# AIRZAI_BASE_BD_REVC_Sheet1.net
KiCad netlist of a schematic drawn in Altium Designer
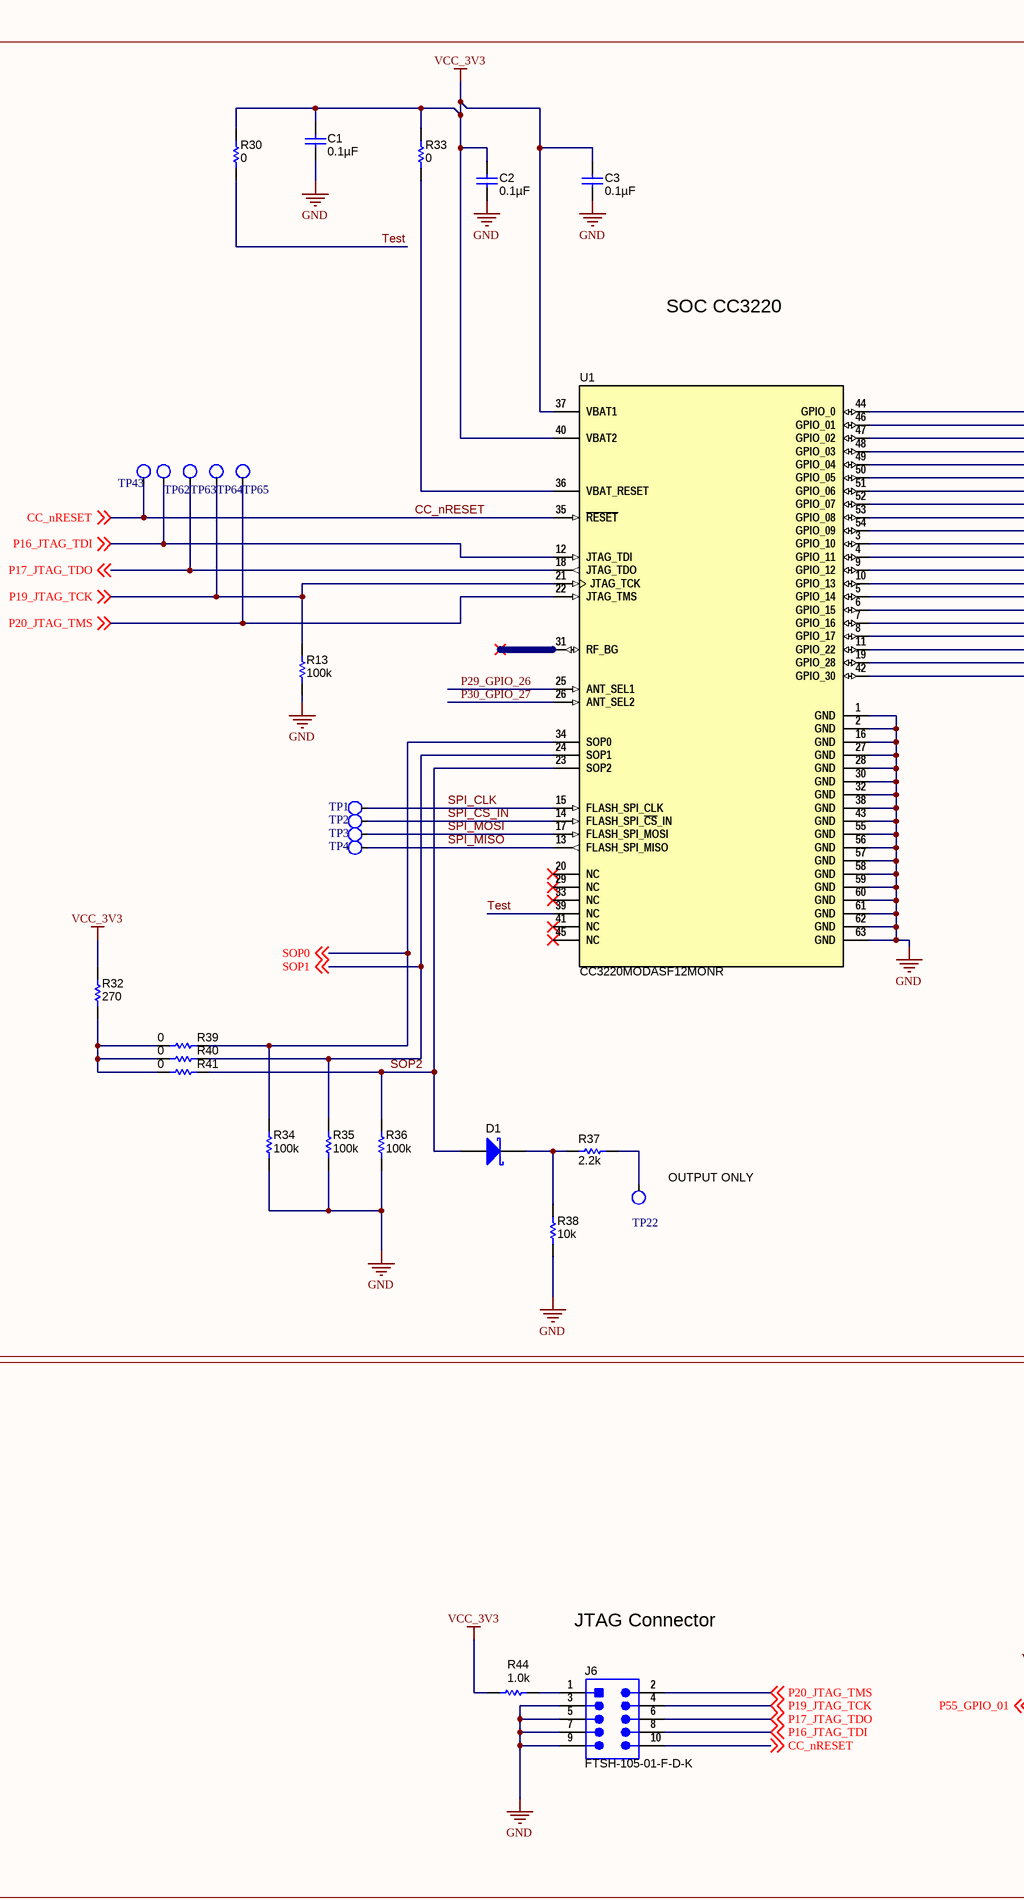
[diagram p0: AIRZAI_BASE_BD_REVC Sheet1.SchDoc, left]
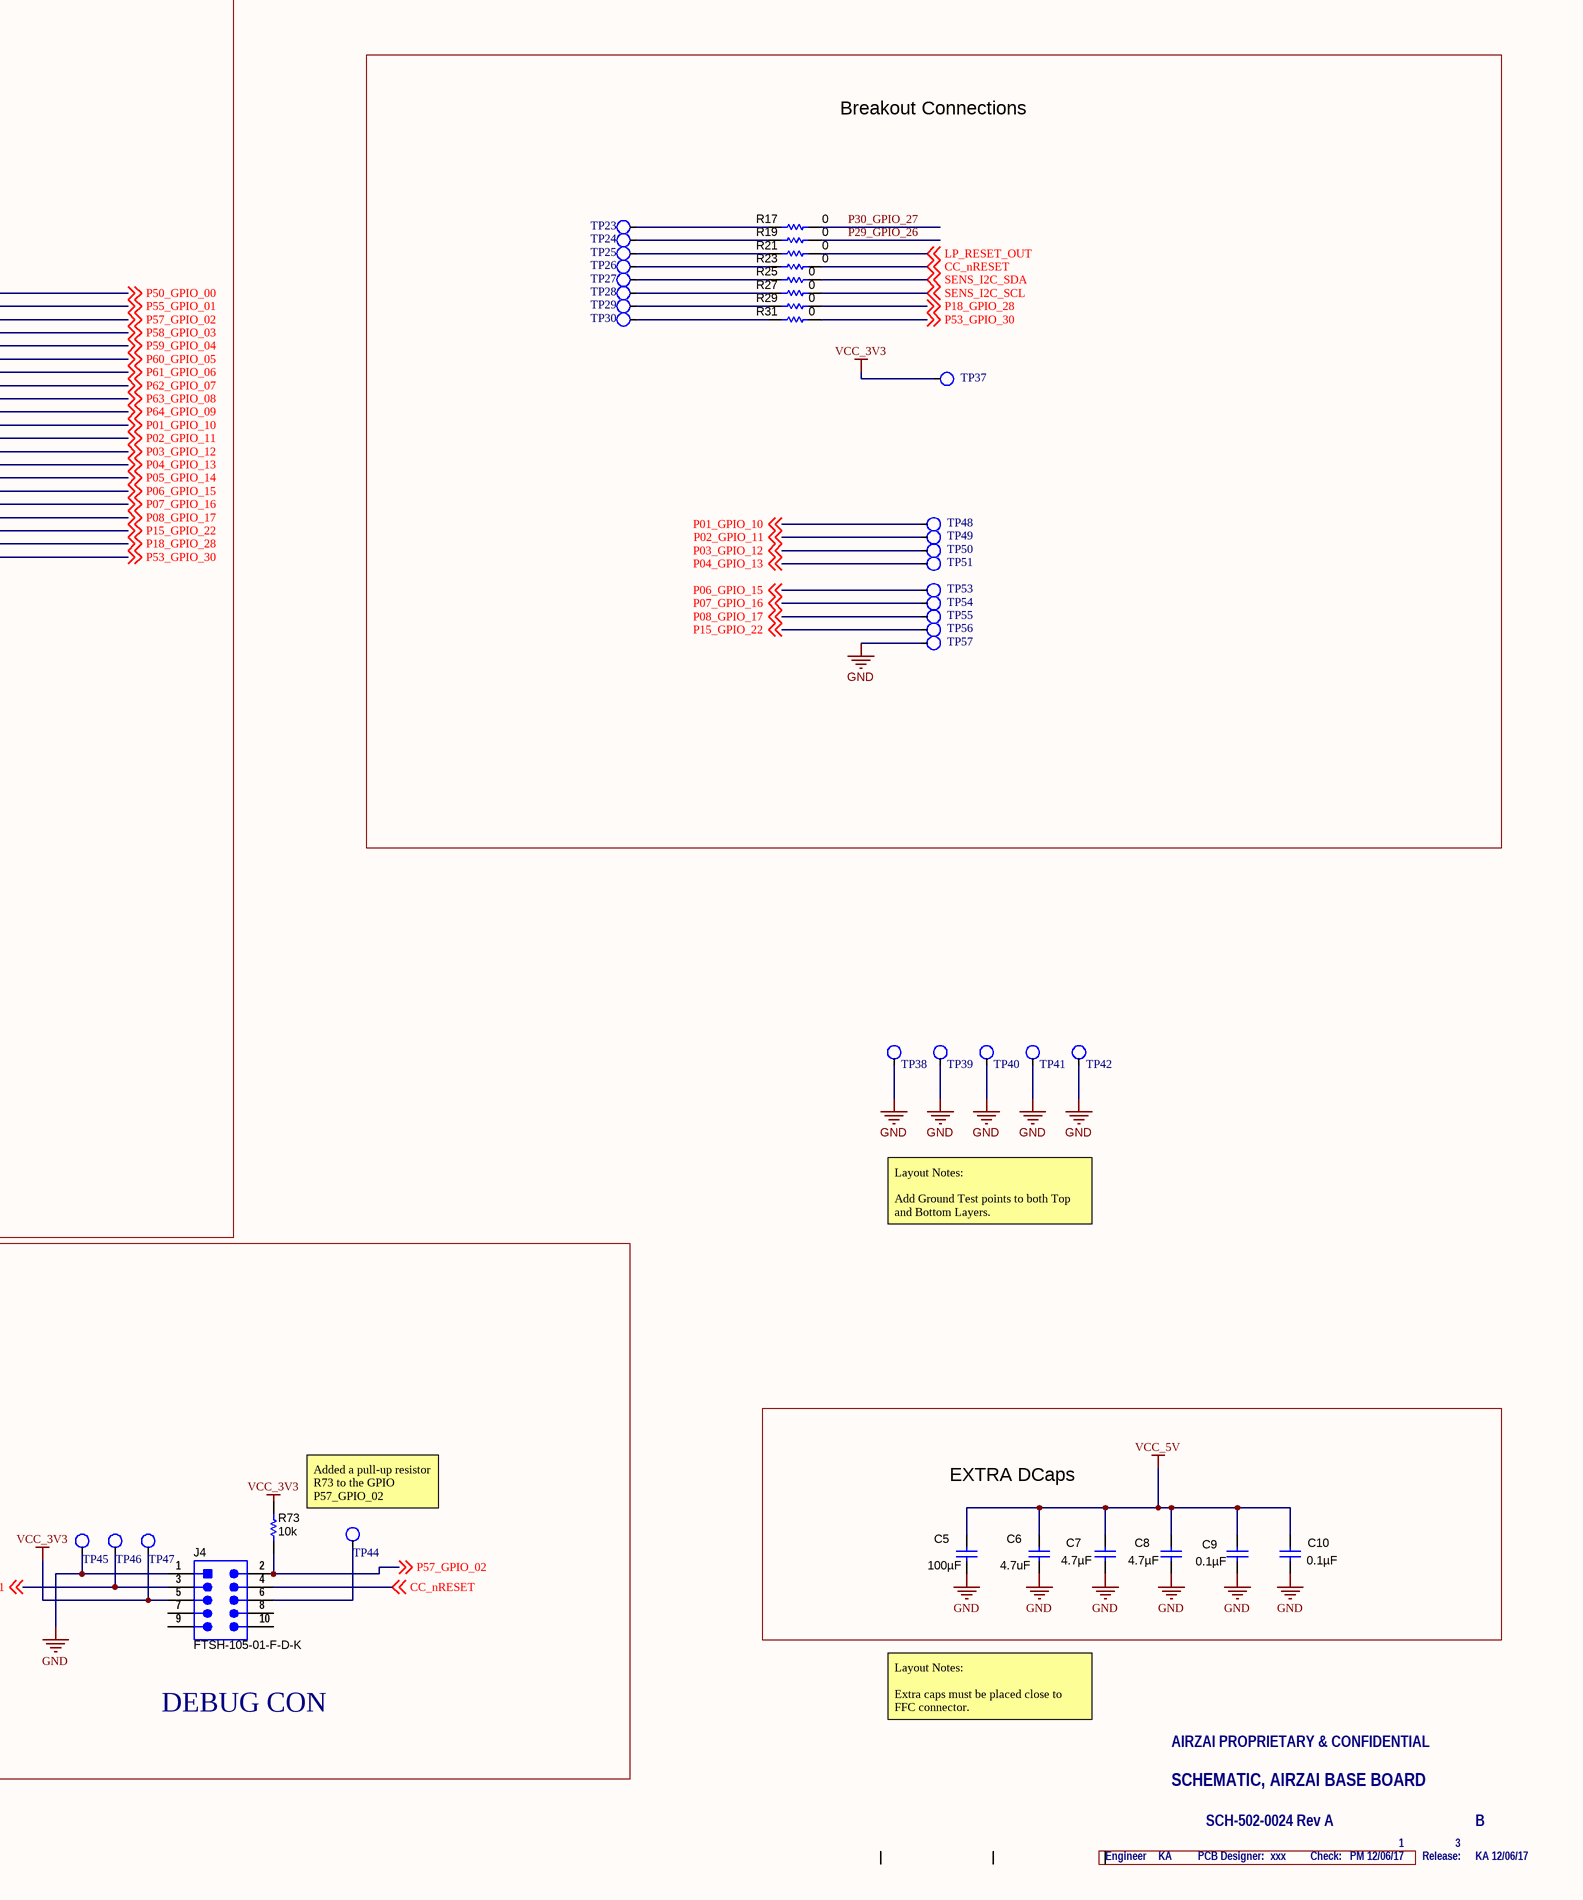
[diagram p1: AIRZAI_BASE_BD_REVC Sheet1.SchDoc, right]

(export (version "E")
  (design (tool "Eeschema 10.0.6"))
  (components
    (comp (ref "C1")
      (value "GRM155R61A104KA01D")
      (footprint "0402")
      (description "CAP, CERM, 0.1 µF, 10 V, +/- 10%, X5R, 0402")
      (fields
        (field (name "VALUEDISPLAYED") "0.1µF")
        (field (name "MANUFACTURER") "MuRata")
        (field (name "PUBLISHER") "Texas Instruments")
      )
      (libsource (lib "Capacitor_Ceramic") (part "GRM155R61A104KA01D"))
    )
    (comp (ref "C2")
      (value "GRM155R61A104KA01D")
      (footprint "0402")
      (description "CAP, CERM, 0.1 µF, 10 V, +/- 10%, X5R, 0402")
      (fields
        (field (name "VALUEDISPLAYED") "0.1µF")
        (field (name "MANUFACTURER") "MuRata")
        (field (name "PUBLISHER") "Texas Instruments")
      )
      (libsource (lib "Capacitor_Ceramic") (part "GRM155R61A104KA01D"))
    )
    (comp (ref "C3")
      (value "GRM155R61A104KA01D")
      (footprint "0402")
      (description "CAP, CERM, 0.1 µF, 10 V, +/- 10%, X5R, 0402")
      (fields
        (field (name "VALUEDISPLAYED") "0.1µF")
        (field (name "MANUFACTURER") "MuRata")
        (field (name "PUBLISHER") "Texas Instruments")
      )
      (libsource (lib "Capacitor_Ceramic") (part "GRM155R61A104KA01D"))
    )
    (comp (ref "C5")
      (value "GRM31CR60J107ME39L")
      (footprint "1206_180")
      (description "CAP, CERM, 100 µF, 6.3 V, +/- 20%, X5R, 1206")
      (fields
        (field (name "VALUEDISPLAYED") "100µF")
        (field (name "MANUFACTURER") "MuRata")
        (field (name "PUBLISHER") "Texas Instruments")
      )
      (libsource (lib "Capacitor_Ceramic") (part "GRM31CR60J107ME39L"))
    )
    (comp (ref "C6")
      (value "4.7uF")
      (footprint "SM0402_BTD.1SM_ACT_H55_CAP_WSS")
      (description "CAP, CERM, 4.7 µF, 6.3 V, +/- 20%, X5R, 0402")
      (fields (field (name "PARTNUMBER") "C1005X5R0J475M050BC") (field (name "MANUFACTURER") "TDK"))
      (libsource (lib "Capacitor_Ceramic") (part "C1005X5R0J475M050BC"))
    )
    (comp (ref "C7")
      (value "C1005X5R0J475M050BC")
      (footprint "SM0402_BTD.1SM_ACT_H55_CAP_WSS")
      (description "CAP, CERM, 4.7 µF, 6.3 V, +/- 20%, X5R, 0402")
      (fields
        (field (name "VALUEDISPLAYED") "4.7µF")
        (field (name "MANUFACTURER") "TDK")
        (field (name "PUBLISHER") "Texas Instruments")
      )
      (libsource (lib "Capacitor_Ceramic") (part "C1005X5R0J475M050BC"))
    )
    (comp (ref "C8")
      (value "C1005X5R0J475M050BC")
      (footprint "SM0402_BTD.1SM_ACT_H55_CAP_WSS")
      (description "CAP, CERM, 4.7 µF, 6.3 V, +/- 20%, X5R, 0402")
      (fields
        (field (name "VALUEDISPLAYED") "4.7µF")
        (field (name "MANUFACTURER") "TDK")
        (field (name "PUBLISHER") "Texas Instruments")
      )
      (libsource (lib "Capacitor_Ceramic") (part "C1005X5R0J475M050BC"))
    )
    (comp (ref "C9")
      (value "C1005X5R1A104K050BA")
      (footprint "SM0402_BTD.1SM_ACT_H55_CAP_WSS")
      (description "CAP, CERM, 0.1 µF, 10 V, +/- 10%, X5R, 0402")
      (fields
        (field (name "VALUEDISPLAYED") "0.1µF")
        (field (name "MANUFACTURER") "TDK")
        (field (name "PUBLISHER") "Texas Instruments")
      )
      (libsource (lib "Capacitor_Ceramic") (part "C1005X5R1A104K050BA"))
    )
    (comp (ref "C10")
      (value "C1005X5R1A104K050BA")
      (footprint "SM0402_BTD.1SM_ACT_H55_CAP_WSS")
      (description "CAP, CERM, 0.1 µF, 10 V, +/- 10%, X5R, 0402")
      (fields
        (field (name "VALUEDISPLAYED") "0.1µF")
        (field (name "MANUFACTURER") "TDK")
        (field (name "PUBLISHER") "Texas Instruments")
      )
      (libsource (lib "Capacitor_Ceramic") (part "C1005X5R1A104K050BA"))
    )
    (comp (ref "D1")
      (value "CD0603-B00340")
      (footprint "Diode_0603")
      (description "Diode, Schottky, 45 V, 0.03 A, 0603 Diode")
      (fields (field (name "MANUFACTURER") "Bourns") (field (name "PUBLISHER") "Texas Instruments"))
      (libsource (lib "Diode") (part "CD0603-B00340"))
    )
    (comp (ref "J4")
      (value "FTSH-105-01-F-D-K")
      (footprint "Samtec_FTSH-105-01-x-D-K")
      (description "Header, 1.27 mm, 5x2, Gold, TH")
      (fields
        (field (name "MANUFACTURER") "Samtec")
        (field (name "SYMBOLCREATOR") "a0412235")
        (field (name "PUBLISHER") "Texas Instruments")
      )
      (libsource (lib "Connectors_Samtec") (part "FTSH-105-01-F-D-K"))
    )
    (comp (ref "J6")
      (value "FTSH-105-01-F-D-K")
      (footprint "Samtec_FTSH-105-01-x-D-K")
      (description "Header, 1.27 mm, 5x2, Gold, TH")
      (fields
        (field (name "MANUFACTURER") "Samtec")
        (field (name "SYMBOLCREATOR") "a0412235")
        (field (name "PUBLISHER") "Texas Instruments")
      )
      (libsource (lib "Connectors_Samtec") (part "FTSH-105-01-F-D-K"))
    )
    (comp (ref "R13")
      (value "CRCW0402100KJNED")
      (footprint "0402")
      (description "RES, 100 k, 5%, 0.063 W, 0402")
      (fields
        (field (name "VALUEDISPLAYED") "100k")
        (field (name "MANUFACTURER") "Vishay-Dale")
        (field (name "PUBLISHER") "Texas Instruments")
      )
      (libsource (lib "Resistor_0402") (part "CRCW0402100KJNED"))
    )
    (comp (ref "R17")
      (value "ERJ-2GE0R00X")
      (footprint "0402")
      (description "RES, 0, 5%, 0.063 W, 0402")
      (fields
        (field (name "VALUEDISPLAYED") "0")
        (field (name "MANUFACTURER") "Panasonic")
        (field (name "PUBLISHER") "Texas Instruments")
      )
      (libsource (lib "Resistor_0402") (part "ERJ-2GE0R00X"))
    )
    (comp (ref "R19")
      (value "ERJ-2GE0R00X")
      (footprint "0402")
      (description "RES, 0, 5%, 0.063 W, 0402")
      (fields
        (field (name "VALUEDISPLAYED") "0")
        (field (name "MANUFACTURER") "Panasonic")
        (field (name "PUBLISHER") "Texas Instruments")
      )
      (libsource (lib "Resistor_0402") (part "ERJ-2GE0R00X"))
    )
    (comp (ref "R21")
      (value "ERJ-2GE0R00X")
      (footprint "0402")
      (description "RES, 0, 5%, 0.063 W, 0402")
      (fields
        (field (name "VALUEDISPLAYED") "0")
        (field (name "MANUFACTURER") "Panasonic")
        (field (name "PUBLISHER") "Texas Instruments")
      )
      (libsource (lib "Resistor_0402") (part "ERJ-2GE0R00X"))
    )
    (comp (ref "R23")
      (value "ERJ-2GE0R00X")
      (footprint "0402")
      (description "RES, 0, 5%, 0.063 W, 0402")
      (fields
        (field (name "VALUEDISPLAYED") "0")
        (field (name "MANUFACTURER") "Panasonic")
        (field (name "PUBLISHER") "Texas Instruments")
      )
      (libsource (lib "Resistor_0402") (part "ERJ-2GE0R00X"))
    )
    (comp (ref "R25")
      (value "ERJ-2GE0R00X")
      (footprint "0402")
      (description "RES, 0, 5%, 0.063 W, 0402")
      (fields
        (field (name "VALUEDISPLAYED") "0")
        (field (name "MANUFACTURER") "Panasonic")
        (field (name "PUBLISHER") "Texas Instruments")
      )
      (libsource (lib "Resistor_0402") (part "ERJ-2GE0R00X"))
    )
    (comp (ref "R27")
      (value "ERJ-2GE0R00X")
      (footprint "0402")
      (description "RES, 0, 5%, 0.063 W, 0402")
      (fields
        (field (name "VALUEDISPLAYED") "0")
        (field (name "MANUFACTURER") "Panasonic")
        (field (name "PUBLISHER") "Texas Instruments")
      )
      (libsource (lib "Resistor_0402") (part "ERJ-2GE0R00X"))
    )
    (comp (ref "R29")
      (value "ERJ-2GE0R00X")
      (footprint "0402")
      (description "RES, 0, 5%, 0.063 W, 0402")
      (fields
        (field (name "VALUEDISPLAYED") "0")
        (field (name "MANUFACTURER") "Panasonic")
        (field (name "PUBLISHER") "Texas Instruments")
      )
      (libsource (lib "Resistor_0402") (part "ERJ-2GE0R00X"))
    )
    (comp (ref "R30")
      (value "RC0603JR-070RL")
      (footprint "0603")
      (description "RES, 0, 5%, 0.1 W, 0603")
      (fields
        (field (name "VALUEDISPLAYED") "0")
        (field (name "MANUFACTURER") "Yageo")
        (field (name "TOLERANCE") "1%")
      )
      (libsource (lib "Resistor_0402") (part "ERJ-2GE0R00X"))
    )
    (comp (ref "R31")
      (value "ERJ-2GE0R00X")
      (footprint "0402")
      (description "RES, 0, 5%, 0.063 W, 0402")
      (fields
        (field (name "VALUEDISPLAYED") "0")
        (field (name "MANUFACTURER") "Panasonic")
        (field (name "PUBLISHER") "Texas Instruments")
      )
      (libsource (lib "Resistor_0402") (part "ERJ-2GE0R00X"))
    )
    (comp (ref "R32")
      (value "CRCW0402270RJNED")
      (footprint "0402")
      (description "RES, 270, 5%, 0.063 W, 0402")
      (fields
        (field (name "VALUEDISPLAYED") "270")
        (field (name "MANUFACTURER") "Vishay-Dale")
        (field (name "PUBLISHER") "Texas Instruments")
      )
      (libsource (lib "Resistor_0402") (part "CRCW0402270RJNED"))
    )
    (comp (ref "R33")
      (value "RC0603JR-070RL")
      (footprint "0603")
      (description "RES, 0, 5%, 0.1 W, 0603")
      (fields
        (field (name "VALUEDISPLAYED") "0")
        (field (name "MANUFACTURER") "Yageo")
        (field (name "TOLERANCE") "1%")
      )
      (libsource (lib "Resistor_0402") (part "ERJ-2GE0R00X"))
    )
    (comp (ref "R34")
      (value "CRCW0402100KJNED")
      (footprint "0402")
      (description "RES, 100 k, 5%, 0.063 W, 0402")
      (fields
        (field (name "VALUEDISPLAYED") "100k")
        (field (name "MANUFACTURER") "Vishay-Dale")
        (field (name "PUBLISHER") "Texas Instruments")
      )
      (libsource (lib "Resistor_0402") (part "CRCW0402100KJNED"))
    )
    (comp (ref "R35")
      (value "CRCW0402100KJNED")
      (footprint "0402")
      (description "RES, 100 k, 5%, 0.063 W, 0402")
      (fields
        (field (name "VALUEDISPLAYED") "100k")
        (field (name "MANUFACTURER") "Vishay-Dale")
        (field (name "PUBLISHER") "Texas Instruments")
      )
      (libsource (lib "Resistor_0402") (part "CRCW0402100KJNED"))
    )
    (comp (ref "R36")
      (value "CRCW0402100KJNED")
      (footprint "0402")
      (description "RES, 100 k, 5%, 0.063 W, 0402")
      (fields
        (field (name "VALUEDISPLAYED") "100k")
        (field (name "MANUFACTURER") "Vishay-Dale")
        (field (name "PUBLISHER") "Texas Instruments")
      )
      (libsource (lib "Resistor_0402") (part "CRCW0402100KJNED"))
    )
    (comp (ref "R37")
      (value "CRCW04022K20JNED")
      (footprint "0402")
      (description "RES, 2.2 k, 5%, 0.063 W, 0402")
      (fields
        (field (name "VALUEDISPLAYED") "2.2k")
        (field (name "MANUFACTURER") "Vishay-Dale")
        (field (name "PUBLISHER") "Texas Instruments")
      )
      (libsource (lib "Resistor_0402") (part "CRCW04022K20JNED"))
    )
    (comp (ref "R38")
      (value "CRCW040210K0JNED")
      (footprint "0402")
      (description "RES, 10 k, 5%, 0.063 W, 0402")
      (fields
        (field (name "VALUEDISPLAYED") "10k")
        (field (name "MANUFACTURER") "Vishay-Dale")
        (field (name "PUBLISHER") "Texas Instruments")
      )
      (libsource (lib "Resistor_0402") (part "CRCW040210K0JNED"))
    )
    (comp (ref "R39")
      (value "RC0603JR-070RL")
      (footprint "0603")
      (description "RES, 0, 5%, 0.1 W, 0603")
      (fields
        (field (name "VALUEDISPLAYED") "0")
        (field (name "MANUFACTURER") "Yageo")
        (field (name "TOLERANCE") "1%")
      )
      (libsource (lib "Resistor_0402") (part "ERJ-2GE0R00X"))
    )
    (comp (ref "R40")
      (value "RC0603JR-070RL")
      (footprint "0603")
      (description "RES, 0, 5%, 0.1 W, 0603")
      (fields
        (field (name "VALUEDISPLAYED") "0")
        (field (name "MANUFACTURER") "Yageo")
        (field (name "TOLERANCE") "1%")
      )
      (libsource (lib "Resistor_0402") (part "ERJ-2GE0R00X"))
    )
    (comp (ref "R41")
      (value "RC0603JR-070RL")
      (footprint "0603")
      (description "RES, 0, 5%, 0.1 W, 0603")
      (fields
        (field (name "VALUEDISPLAYED") "0")
        (field (name "MANUFACTURER") "Yageo")
        (field (name "TOLERANCE") "1%")
      )
      (libsource (lib "Resistor_0402") (part "ERJ-2GE0R00X"))
    )
    (comp (ref "R44")
      (value "CRCW04021K00JNED")
      (footprint "0402")
      (description "RES, 1.0 k, 5%, 0.063 W, 0402")
      (fields
        (field (name "VALUEDISPLAYED") "1.0k")
        (field (name "MANUFACTURER") "Vishay-Dale")
        (field (name "PUBLISHER") "Texas Instruments")
      )
      (libsource (lib "Resistor_0402") (part "CRCW04021K00JNED"))
    )
    (comp (ref "R73")
      (value "CRCW040210K0JNED")
      (footprint "0402")
      (description "RES, 10 k, 5%, 0.063 W, 0402")
      (fields
        (field (name "VALUEDISPLAYED") "10k")
        (field (name "MANUFACTURER") "Vishay-Dale")
        (field (name "PUBLISHER") "Texas Instruments")
      )
      (libsource (lib "Resistor_0402") (part "CRCW040210K0JNED"))
    )
    (comp (ref "TP1")
      (value "WIREPT")
      (footprint "TP_0.9MM")
      (libsource (lib "EAGLE_CAD_Library") (part "WIREPT"))
    )
    (comp (ref "TP2")
      (value "WIREPT")
      (footprint "TP_0.9MM")
      (libsource (lib "EAGLE_CAD_Library") (part "WIREPT"))
    )
    (comp (ref "TP3")
      (value "WIREPT")
      (footprint "TP_0.9MM")
      (libsource (lib "EAGLE_CAD_Library") (part "WIREPT"))
    )
    (comp (ref "TP4")
      (value "WIREPT")
      (footprint "TP_0.9MM")
      (libsource (lib "EAGLE_CAD_Library") (part "WIREPT"))
    )
    (comp (ref "TP22")
      (value "WIREPT")
      (footprint "TP_0.9MM")
      (libsource (lib "EAGLE_CAD_Library") (part "WIREPT"))
    )
    (comp (ref "TP23")
      (value "WIREPT")
      (footprint "TP_0.9MM")
      (libsource (lib "EAGLE_CAD_Library") (part "WIREPT"))
    )
    (comp (ref "TP24")
      (value "WIREPT")
      (footprint "TP_0.9MM")
      (libsource (lib "EAGLE_CAD_Library") (part "WIREPT"))
    )
    (comp (ref "TP25")
      (value "WIREPT")
      (footprint "TP_0.9MM")
      (libsource (lib "EAGLE_CAD_Library") (part "WIREPT"))
    )
    (comp (ref "TP26")
      (value "WIREPT")
      (footprint "TP_0.9MM")
      (libsource (lib "EAGLE_CAD_Library") (part "WIREPT"))
    )
    (comp (ref "TP27")
      (value "WIREPT")
      (footprint "TP_0.9MM")
      (libsource (lib "EAGLE_CAD_Library") (part "WIREPT"))
    )
    (comp (ref "TP28")
      (value "WIREPT")
      (footprint "TP_0.9MM")
      (libsource (lib "EAGLE_CAD_Library") (part "WIREPT"))
    )
    (comp (ref "TP29")
      (value "WIREPT")
      (footprint "TP_0.9MM")
      (libsource (lib "EAGLE_CAD_Library") (part "WIREPT"))
    )
    (comp (ref "TP30")
      (value "WIREPT")
      (footprint "TP_0.9MM")
      (libsource (lib "EAGLE_CAD_Library") (part "WIREPT"))
    )
    (comp (ref "TP37")
      (value "WIREPT")
      (footprint "TP_0.9MM")
      (libsource (lib "EAGLE_CAD_Library") (part "WIREPT"))
    )
    (comp (ref "TP38")
      (value "WIREPT")
      (footprint "TP_0.9MM")
      (libsource (lib "EAGLE_CAD_Library") (part "WIREPT"))
    )
    (comp (ref "TP39")
      (value "WIREPT")
      (footprint "TP_0.9MM")
      (libsource (lib "EAGLE_CAD_Library") (part "WIREPT"))
    )
    (comp (ref "TP40")
      (value "WIREPT")
      (footprint "TP_0.9MM")
      (libsource (lib "EAGLE_CAD_Library") (part "WIREPT"))
    )
    (comp (ref "TP41")
      (value "WIREPT")
      (footprint "TP_0.9MM")
      (libsource (lib "EAGLE_CAD_Library") (part "WIREPT"))
    )
    (comp (ref "TP42")
      (value "WIREPT")
      (footprint "TP_0.9MM")
      (libsource (lib "EAGLE_CAD_Library") (part "WIREPT"))
    )
    (comp (ref "TP43")
      (value "WIREPT")
      (footprint "TP_0.9MM")
      (libsource (lib "EAGLE_CAD_Library") (part "WIREPT"))
    )
    (comp (ref "TP44")
      (value "WIREPT")
      (footprint "TP_0.9MM")
      (libsource (lib "EAGLE_CAD_Library") (part "WIREPT"))
    )
    (comp (ref "TP45")
      (value "WIREPT")
      (footprint "TP_0.9MM")
      (libsource (lib "EAGLE_CAD_Library") (part "WIREPT"))
    )
    (comp (ref "TP46")
      (value "WIREPT")
      (footprint "TP_0.9MM")
      (libsource (lib "EAGLE_CAD_Library") (part "WIREPT"))
    )
    (comp (ref "TP47")
      (value "WIREPT")
      (footprint "TP_0.9MM")
      (libsource (lib "EAGLE_CAD_Library") (part "WIREPT"))
    )
    (comp (ref "TP48")
      (value "WIREPT")
      (footprint "TP_0.9MM")
      (libsource (lib "EAGLE_CAD_Library") (part "WIREPT"))
    )
    (comp (ref "TP49")
      (value "WIREPT")
      (footprint "TP_0.9MM")
      (libsource (lib "EAGLE_CAD_Library") (part "WIREPT"))
    )
    (comp (ref "TP50")
      (value "WIREPT")
      (footprint "TP_0.9MM")
      (libsource (lib "EAGLE_CAD_Library") (part "WIREPT"))
    )
    (comp (ref "TP51")
      (value "WIREPT")
      (footprint "TP_0.9MM")
      (libsource (lib "EAGLE_CAD_Library") (part "WIREPT"))
    )
    (comp (ref "TP53")
      (value "WIREPT")
      (footprint "TP_0.9MM")
      (libsource (lib "EAGLE_CAD_Library") (part "WIREPT"))
    )
    (comp (ref "TP54")
      (value "WIREPT")
      (footprint "TP_0.9MM")
      (libsource (lib "EAGLE_CAD_Library") (part "WIREPT"))
    )
    (comp (ref "TP55")
      (value "WIREPT")
      (footprint "TP_0.9MM")
      (libsource (lib "EAGLE_CAD_Library") (part "WIREPT"))
    )
    (comp (ref "TP56")
      (value "WIREPT")
      (footprint "TP_0.9MM")
      (libsource (lib "EAGLE_CAD_Library") (part "WIREPT"))
    )
    (comp (ref "TP57")
      (value "WIREPT")
      (footprint "TP_0.9MM")
      (libsource (lib "EAGLE_CAD_Library") (part "WIREPT"))
    )
    (comp (ref "TP62")
      (value "WIREPT")
      (footprint "TP_0.9MM")
      (libsource (lib "EAGLE_CAD_Library") (part "WIREPT"))
    )
    (comp (ref "TP63")
      (value "WIREPT")
      (footprint "TP_0.9MM")
      (libsource (lib "EAGLE_CAD_Library") (part "WIREPT"))
    )
    (comp (ref "TP64")
      (value "WIREPT")
      (footprint "TP_0.9MM")
      (libsource (lib "EAGLE_CAD_Library") (part "WIREPT"))
    )
    (comp (ref "TP65")
      (value "WIREPT")
      (footprint "TP_0.9MM")
      (libsource (lib "EAGLE_CAD_Library") (part "WIREPT"))
    )
    (comp (ref "U1")
      (value "CC3220MODASF12MONR")
      (footprint "MON0063A")
      (fields
        (field (name "ALTERNATE PARTNUMBER") "XCC3220MODASF12MONR")
        (field (name "MANUFACTURER") "Texas Instruments")
        (field (name "SYMBOLCREATOR") "Altium")
        (field (name "PUBLISHER") "Texas Instruments")
      )
      (libsource (lib "TI_Pre_RTM") (part "CC3220MODASF12MONR"))
    )
  )
  (nets
    (net (code "1") (name "/P29_GPIO_26") (class "Default")
      (node (ref "R19") (pin "2") (pinfunction "2_2") (pintype "passive"))
      (node (ref "U1") (pin "25") (pinfunction "ANT_SEL1_25") (pintype "input"))
    )
    (net (code "2") (name "/P30_GPIO_27") (class "Default")
      (node (ref "R17") (pin "2") (pinfunction "2_2") (pintype "passive"))
      (node (ref "U1") (pin "26") (pinfunction "ANT_SEL2_26") (pintype "input"))
    )
    (net (code "3") (name "/SOP2") (class "Default")
      (node (ref "D1") (pin "2") (pinfunction "A_2") (pintype "passive"))
      (node (ref "R36") (pin "1") (pinfunction "1_1") (pintype "passive"))
      (node (ref "R41") (pin "1") (pinfunction "1_1") (pintype "passive"))
      (node (ref "U1") (pin "23") (pinfunction "SOP2_23") (pintype "passive"))
    )
    (net (code "4") (name "/SPI_CLK") (class "Default")
      (node (ref "TP1") (pin "1") (pinfunction "1_1") (pintype "passive"))
      (node (ref "U1") (pin "15") (pinfunction "FLASH_SPI_CLK_15") (pintype "input"))
    )
    (net (code "5") (name "/SPI_CS_IN") (class "Default")
      (node (ref "TP2") (pin "1") (pinfunction "1_1") (pintype "passive"))
      (node (ref "U1") (pin "14") (pinfunction "FLASH_SPI_~{CS}_IN_14") (pintype "input"))
    )
    (net (code "6") (name "/SPI_MISO") (class "Default")
      (node (ref "TP4") (pin "1") (pinfunction "1_1") (pintype "passive"))
      (node (ref "U1") (pin "13") (pinfunction "FLASH_SPI_MISO_13") (pintype "output"))
    )
    (net (code "7") (name "/SPI_MOSI") (class "Default")
      (node (ref "TP3") (pin "1") (pinfunction "1_1") (pintype "passive"))
      (node (ref "U1") (pin "17") (pinfunction "FLASH_SPI_MOSI_17") (pintype "input"))
    )
    (net (code "8") (name "/Test") (class "Default")
      (node (ref "R30") (pin "1") (pinfunction "1_1") (pintype "passive"))
      (node (ref "U1") (pin "39") (pinfunction "NC_39") (pintype "passive"))
    )
    (net (code "9") (name "CC_nRESET") (class "Default")
      (node (ref "J4") (pin "4") (pinfunction "4_4") (pintype "passive"))
      (node (ref "J6") (pin "10") (pinfunction "10_10") (pintype "passive"))
      (node (ref "R23") (pin "2") (pinfunction "2_2") (pintype "passive"))
      (node (ref "TP43") (pin "1") (pinfunction "1_1") (pintype "passive"))
      (node (ref "U1") (pin "35") (pinfunction "RESET_35") (pintype "input"))
    )
    (net (code "10") (name "GND") (class "Default")
      (node (ref "C1") (pin "2") (pinfunction "2_2") (pintype "passive"))
      (node (ref "C10") (pin "2") (pinfunction "2_2") (pintype "passive"))
      (node (ref "C2") (pin "2") (pinfunction "2_2") (pintype "passive"))
      (node (ref "C3") (pin "2") (pinfunction "2_2") (pintype "passive"))
      (node (ref "C5") (pin "2") (pinfunction "2_2") (pintype "passive"))
      (node (ref "C6") (pin "2") (pinfunction "2_2") (pintype "passive"))
      (node (ref "C7") (pin "2") (pinfunction "2_2") (pintype "passive"))
      (node (ref "C8") (pin "2") (pinfunction "2_2") (pintype "passive"))
      (node (ref "C9") (pin "2") (pinfunction "2_2") (pintype "passive"))
      (node (ref "J4") (pin "1") (pinfunction "1_1") (pintype "passive"))
      (node (ref "J6") (pin "3") (pinfunction "3_3") (pintype "passive"))
      (node (ref "J6") (pin "5") (pinfunction "5_5") (pintype "passive"))
      (node (ref "J6") (pin "7") (pinfunction "7_7") (pintype "passive"))
      (node (ref "J6") (pin "9") (pinfunction "9_9") (pintype "passive"))
      (node (ref "R13") (pin "2") (pinfunction "2_2") (pintype "passive"))
      (node (ref "R34") (pin "1") (pinfunction "1_1") (pintype "passive"))
      (node (ref "R35") (pin "2") (pinfunction "2_2") (pintype "passive"))
      (node (ref "R36") (pin "2") (pinfunction "2_2") (pintype "passive"))
      (node (ref "R38") (pin "2") (pinfunction "2_2") (pintype "passive"))
      (node (ref "TP38") (pin "1") (pinfunction "1_1") (pintype "passive"))
      (node (ref "TP39") (pin "1") (pinfunction "1_1") (pintype "passive"))
      (node (ref "TP40") (pin "1") (pinfunction "1_1") (pintype "passive"))
      (node (ref "TP41") (pin "1") (pinfunction "1_1") (pintype "passive"))
      (node (ref "TP42") (pin "1") (pinfunction "1_1") (pintype "passive"))
      (node (ref "TP45") (pin "1") (pinfunction "1_1") (pintype "passive"))
      (node (ref "TP57") (pin "1") (pinfunction "1_1") (pintype "passive"))
      (node (ref "U1") (pin "1") (pinfunction "GND_1") (pintype "power_in"))
      (node (ref "U1") (pin "16") (pinfunction "GND_16") (pintype "power_in"))
      (node (ref "U1") (pin "2") (pinfunction "GND_2") (pintype "power_in"))
      (node (ref "U1") (pin "27") (pinfunction "GND_27") (pintype "power_in"))
      (node (ref "U1") (pin "28") (pinfunction "GND_28") (pintype "power_in"))
      (node (ref "U1") (pin "30") (pinfunction "GND_30") (pintype "power_in"))
      (node (ref "U1") (pin "32") (pinfunction "GND_32") (pintype "power_in"))
      (node (ref "U1") (pin "38") (pinfunction "GND_38") (pintype "power_in"))
      (node (ref "U1") (pin "43") (pinfunction "GND_43") (pintype "power_in"))
      (node (ref "U1") (pin "55") (pinfunction "GND_55") (pintype "power_in"))
      (node (ref "U1") (pin "56") (pinfunction "GND_56") (pintype "power_in"))
      (node (ref "U1") (pin "57") (pinfunction "GND_57") (pintype "power_in"))
      (node (ref "U1") (pin "58") (pinfunction "GND_58") (pintype "power_in"))
      (node (ref "U1") (pin "59") (pinfunction "GND_59") (pintype "power_in"))
      (node (ref "U1") (pin "60") (pinfunction "GND_60") (pintype "power_in"))
      (node (ref "U1") (pin "61") (pinfunction "GND_61") (pintype "power_in"))
      (node (ref "U1") (pin "62") (pinfunction "GND_62") (pintype "power_in"))
      (node (ref "U1") (pin "63") (pinfunction "GND_63") (pintype "power_in"))
    )
    (net (code "11") (name "LP_RESET_OUT") (class "Default")
      (node (ref "R21") (pin "2") (pinfunction "2_2") (pintype "passive"))
    )
    (net (code "12") (name "Net-(D1-K)") (class "Default")
      (node (ref "D1") (pin "1") (pinfunction "K_1") (pintype "passive"))
      (node (ref "R37") (pin "1") (pinfunction "1_1") (pintype "passive"))
      (node (ref "R38") (pin "1") (pinfunction "1_1") (pintype "passive"))
    )
    (net (code "13") (name "Net-(J4-Pad6)") (class "Default")
      (node (ref "J4") (pin "6") (pinfunction "6_6") (pintype "passive"))
      (node (ref "TP44") (pin "1") (pinfunction "1_1") (pintype "passive"))
    )
    (net (code "14") (name "Net-(J6-Pad1)") (class "Default")
      (node (ref "J6") (pin "1") (pinfunction "1_1") (pintype "passive"))
      (node (ref "R44") (pin "2") (pinfunction "2_2") (pintype "passive"))
    )
    (net (code "15") (name "Net-(R17-Pad1)") (class "Default")
      (node (ref "R17") (pin "1") (pinfunction "1_1") (pintype "passive"))
      (node (ref "TP23") (pin "1") (pinfunction "1_1") (pintype "passive"))
    )
    (net (code "16") (name "Net-(R19-Pad1)") (class "Default")
      (node (ref "R19") (pin "1") (pinfunction "1_1") (pintype "passive"))
      (node (ref "TP24") (pin "1") (pinfunction "1_1") (pintype "passive"))
    )
    (net (code "17") (name "Net-(R21-Pad1)") (class "Default")
      (node (ref "R21") (pin "1") (pinfunction "1_1") (pintype "passive"))
      (node (ref "TP25") (pin "1") (pinfunction "1_1") (pintype "passive"))
    )
    (net (code "18") (name "Net-(R23-Pad1)") (class "Default")
      (node (ref "R23") (pin "1") (pinfunction "1_1") (pintype "passive"))
      (node (ref "TP26") (pin "1") (pinfunction "1_1") (pintype "passive"))
    )
    (net (code "19") (name "Net-(R25-Pad1)") (class "Default")
      (node (ref "R25") (pin "1") (pinfunction "1_1") (pintype "passive"))
      (node (ref "TP27") (pin "1") (pinfunction "1_1") (pintype "passive"))
    )
    (net (code "20") (name "Net-(R27-Pad1)") (class "Default")
      (node (ref "R27") (pin "1") (pinfunction "1_1") (pintype "passive"))
      (node (ref "TP28") (pin "1") (pinfunction "1_1") (pintype "passive"))
    )
    (net (code "21") (name "Net-(R29-Pad1)") (class "Default")
      (node (ref "R29") (pin "1") (pinfunction "1_1") (pintype "passive"))
      (node (ref "TP29") (pin "1") (pinfunction "1_1") (pintype "passive"))
    )
    (net (code "22") (name "Net-(R31-Pad1)") (class "Default")
      (node (ref "R31") (pin "1") (pinfunction "1_1") (pintype "passive"))
      (node (ref "TP30") (pin "1") (pinfunction "1_1") (pintype "passive"))
    )
    (net (code "23") (name "Net-(R32-Pad2)") (class "Default")
      (node (ref "R32") (pin "2") (pinfunction "2_2") (pintype "passive"))
      (node (ref "R39") (pin "2") (pinfunction "2_2") (pintype "passive"))
      (node (ref "R40") (pin "2") (pinfunction "2_2") (pintype "passive"))
      (node (ref "R41") (pin "2") (pinfunction "2_2") (pintype "passive"))
    )
    (net (code "24") (name "Net-(R37-Pad2)") (class "Default")
      (node (ref "R37") (pin "2") (pinfunction "2_2") (pintype "passive"))
      (node (ref "TP22") (pin "1") (pinfunction "1_1") (pintype "passive"))
    )
    (net (code "25") (name "Net-(U1-VBAT_RESET)") (class "Default")
      (node (ref "R33") (pin "1") (pinfunction "1_1") (pintype "passive"))
      (node (ref "U1") (pin "36") (pinfunction "VBAT_RESET_36") (pintype "passive"))
    )
    (net (code "26") (name "P01_GPIO_10") (class "Default")
      (node (ref "TP48") (pin "1") (pinfunction "1_1") (pintype "passive"))
      (node (ref "U1") (pin "3") (pinfunction "GPIO_10_3") (pintype "bidirectional"))
    )
    (net (code "27") (name "P02_GPIO_11") (class "Default")
      (node (ref "TP49") (pin "1") (pinfunction "1_1") (pintype "passive"))
      (node (ref "U1") (pin "4") (pinfunction "GPIO_11_4") (pintype "bidirectional"))
    )
    (net (code "28") (name "P03_GPIO_12") (class "Default")
      (node (ref "TP50") (pin "1") (pinfunction "1_1") (pintype "passive"))
      (node (ref "U1") (pin "9") (pinfunction "GPIO_12_9") (pintype "bidirectional"))
    )
    (net (code "29") (name "P04_GPIO_13") (class "Default")
      (node (ref "TP51") (pin "1") (pinfunction "1_1") (pintype "passive"))
      (node (ref "U1") (pin "10") (pinfunction "GPIO_13_10") (pintype "bidirectional"))
    )
    (net (code "30") (name "P05_GPIO_14") (class "Default")
      (node (ref "U1") (pin "5") (pinfunction "GPIO_14_5") (pintype "bidirectional"))
    )
    (net (code "31") (name "P06_GPIO_15") (class "Default")
      (node (ref "TP53") (pin "1") (pinfunction "1_1") (pintype "passive"))
      (node (ref "U1") (pin "6") (pinfunction "GPIO_15_6") (pintype "bidirectional"))
    )
    (net (code "32") (name "P07_GPIO_16") (class "Default")
      (node (ref "TP54") (pin "1") (pinfunction "1_1") (pintype "passive"))
      (node (ref "U1") (pin "7") (pinfunction "GPIO_16_7") (pintype "bidirectional"))
    )
    (net (code "33") (name "P08_GPIO_17") (class "Default")
      (node (ref "TP55") (pin "1") (pinfunction "1_1") (pintype "passive"))
      (node (ref "U1") (pin "8") (pinfunction "GPIO_17_8") (pintype "bidirectional"))
    )
    (net (code "34") (name "P15_GPIO_22") (class "Default")
      (node (ref "TP56") (pin "1") (pinfunction "1_1") (pintype "passive"))
      (node (ref "U1") (pin "11") (pinfunction "GPIO_22_11") (pintype "bidirectional"))
    )
    (net (code "35") (name "P16_JTAG_TDI") (class "Default")
      (node (ref "J6") (pin "8") (pinfunction "8_8") (pintype "passive"))
      (node (ref "TP62") (pin "1") (pinfunction "1_1") (pintype "passive"))
      (node (ref "U1") (pin "12") (pinfunction "JTAG_TDI_12") (pintype "input"))
    )
    (net (code "36") (name "P17_JTAG_TDO") (class "Default")
      (node (ref "J6") (pin "6") (pinfunction "6_6") (pintype "passive"))
      (node (ref "TP63") (pin "1") (pinfunction "1_1") (pintype "passive"))
      (node (ref "U1") (pin "18") (pinfunction "JTAG_TDO_18") (pintype "output"))
    )
    (net (code "37") (name "P18_GPIO_28") (class "Default")
      (node (ref "R29") (pin "2") (pinfunction "2_2") (pintype "passive"))
      (node (ref "U1") (pin "19") (pinfunction "GPIO_28_19") (pintype "bidirectional"))
    )
    (net (code "38") (name "P19_JTAG_TCK") (class "Default")
      (node (ref "J6") (pin "4") (pinfunction "4_4") (pintype "passive"))
      (node (ref "R13") (pin "1") (pinfunction "1_1") (pintype "passive"))
      (node (ref "TP64") (pin "1") (pinfunction "1_1") (pintype "passive"))
      (node (ref "U1") (pin "21") (pinfunction "JTAG_TCK_21") (pintype "input"))
    )
    (net (code "39") (name "P20_JTAG_TMS") (class "Default")
      (node (ref "J6") (pin "2") (pinfunction "2_2") (pintype "passive"))
      (node (ref "TP65") (pin "1") (pinfunction "1_1") (pintype "passive"))
      (node (ref "U1") (pin "22") (pinfunction "JTAG_TMS_22") (pintype "input"))
    )
    (net (code "40") (name "P50_GPIO_00") (class "Default")
      (node (ref "U1") (pin "44") (pinfunction "GPIO_0_44") (pintype "bidirectional"))
    )
    (net (code "41") (name "P53_GPIO_30") (class "Default")
      (node (ref "R31") (pin "2") (pinfunction "2_2") (pintype "passive"))
      (node (ref "U1") (pin "42") (pinfunction "GPIO_30_42") (pintype "bidirectional"))
    )
    (net (code "42") (name "P55_GPIO_01") (class "Default")
      (node (ref "J4") (pin "3") (pinfunction "3_3") (pintype "passive"))
      (node (ref "TP46") (pin "1") (pinfunction "1_1") (pintype "passive"))
      (node (ref "U1") (pin "46") (pinfunction "GPIO_01_46") (pintype "bidirectional"))
    )
    (net (code "43") (name "P57_GPIO_02") (class "Default")
      (node (ref "J4") (pin "2") (pinfunction "2_2") (pintype "passive"))
      (node (ref "R73") (pin "2") (pinfunction "2_2") (pintype "passive"))
      (node (ref "U1") (pin "47") (pinfunction "GPIO_02_47") (pintype "bidirectional"))
    )
    (net (code "44") (name "P58_GPIO_03") (class "Default")
      (node (ref "U1") (pin "48") (pinfunction "GPIO_03_48") (pintype "bidirectional"))
    )
    (net (code "45") (name "P59_GPIO_04") (class "Default")
      (node (ref "U1") (pin "49") (pinfunction "GPIO_04_49") (pintype "bidirectional"))
    )
    (net (code "46") (name "P60_GPIO_05") (class "Default")
      (node (ref "U1") (pin "50") (pinfunction "GPIO_05_50") (pintype "bidirectional"))
    )
    (net (code "47") (name "P61_GPIO_06") (class "Default")
      (node (ref "U1") (pin "51") (pinfunction "GPIO_06_51") (pintype "bidirectional"))
    )
    (net (code "48") (name "P62_GPIO_07") (class "Default")
      (node (ref "U1") (pin "52") (pinfunction "GPIO_07_52") (pintype "bidirectional"))
    )
    (net (code "49") (name "P63_GPIO_08") (class "Default")
      (node (ref "U1") (pin "53") (pinfunction "GPIO_08_53") (pintype "bidirectional"))
    )
    (net (code "50") (name "P64_GPIO_09") (class "Default")
      (node (ref "U1") (pin "54") (pinfunction "GPIO_09_54") (pintype "bidirectional"))
    )
    (net (code "51") (name "SENS_I2C_SCL") (class "Default")
      (node (ref "R27") (pin "2") (pinfunction "2_2") (pintype "passive"))
    )
    (net (code "52") (name "SENS_I2C_SDA") (class "Default")
      (node (ref "R25") (pin "2") (pinfunction "2_2") (pintype "passive"))
    )
    (net (code "53") (name "SOP0") (class "Default")
      (node (ref "R34") (pin "2") (pinfunction "2_2") (pintype "passive"))
      (node (ref "R39") (pin "1") (pinfunction "1_1") (pintype "passive"))
      (node (ref "U1") (pin "34") (pinfunction "SOP0_34") (pintype "passive"))
    )
    (net (code "54") (name "SOP1") (class "Default")
      (node (ref "R35") (pin "1") (pinfunction "1_1") (pintype "passive"))
      (node (ref "R40") (pin "1") (pinfunction "1_1") (pintype "passive"))
      (node (ref "U1") (pin "24") (pinfunction "SOP1_24") (pintype "passive"))
    )
    (net (code "55") (name "VCC_3V3") (class "Default")
      (node (ref "C1") (pin "1") (pinfunction "1_1") (pintype "passive"))
      (node (ref "C2") (pin "1") (pinfunction "1_1") (pintype "passive"))
      (node (ref "C3") (pin "1") (pinfunction "1_1") (pintype "passive"))
      (node (ref "J4") (pin "5") (pinfunction "5_5") (pintype "passive"))
      (node (ref "R30") (pin "2") (pinfunction "2_2") (pintype "passive"))
      (node (ref "R32") (pin "1") (pinfunction "1_1") (pintype "passive"))
      (node (ref "R33") (pin "2") (pinfunction "2_2") (pintype "passive"))
      (node (ref "R44") (pin "1") (pinfunction "1_1") (pintype "passive"))
      (node (ref "TP37") (pin "1") (pinfunction "1_1") (pintype "passive"))
      (node (ref "TP47") (pin "1") (pinfunction "1_1") (pintype "passive"))
      (node (ref "U1") (pin "37") (pinfunction "VBAT1_37") (pintype "power_in"))
      (node (ref "U1") (pin "40") (pinfunction "VBAT2_40") (pintype "power_in"))
    )
    (net (code "56") (name "VCC_5V") (class "Default")
      (node (ref "C10") (pin "1") (pinfunction "1_1") (pintype "passive"))
      (node (ref "C5") (pin "1") (pinfunction "1_1") (pintype "passive"))
      (node (ref "C6") (pin "1") (pinfunction "1_1") (pintype "passive"))
      (node (ref "C7") (pin "1") (pinfunction "1_1") (pintype "passive"))
      (node (ref "C8") (pin "1") (pinfunction "1_1") (pintype "passive"))
      (node (ref "C9") (pin "1") (pinfunction "1_1") (pintype "passive"))
    )
    (net (code "57") (name "unconnected-(J4-Pad7)") (class "Default")
      (node (ref "J4") (pin "7") (pinfunction "7_7") (pintype "passive"))
    )
    (net (code "58") (name "unconnected-(J4-Pad8)") (class "Default")
      (node (ref "J4") (pin "8") (pinfunction "8_8") (pintype "passive"))
    )
    (net (code "59") (name "unconnected-(J4-Pad9)") (class "Default")
      (node (ref "J4") (pin "9") (pinfunction "9_9") (pintype "passive"))
    )
    (net (code "60") (name "unconnected-(J4-Pad10)") (class "Default")
      (node (ref "J4") (pin "10") (pinfunction "10_10") (pintype "passive"))
    )
    (net (code "61") (name "unconnected-(R73-Pad1)") (class "Default")
      (node (ref "R73") (pin "1") (pinfunction "1_1") (pintype "passive"))
    )
    (net (code "62") (name "unconnected-(U1-NC-Pad20)") (class "Default")
      (node (ref "U1") (pin "20") (pinfunction "NC_20") (pintype "passive+no_connect"))
    )
    (net (code "63") (name "unconnected-(U1-NC-Pad29)") (class "Default")
      (node (ref "U1") (pin "29") (pinfunction "NC_29") (pintype "passive+no_connect"))
    )
    (net (code "64") (name "unconnected-(U1-NC-Pad33)") (class "Default")
      (node (ref "U1") (pin "33") (pinfunction "NC_33") (pintype "passive+no_connect"))
    )
    (net (code "65") (name "unconnected-(U1-NC-Pad41)") (class "Default")
      (node (ref "U1") (pin "41") (pinfunction "NC_41") (pintype "passive+no_connect"))
    )
    (net (code "66") (name "unconnected-(U1-NC-Pad45)") (class "Default")
      (node (ref "U1") (pin "45") (pinfunction "NC_45") (pintype "passive+no_connect"))
    )
    (net (code "67") (name "unconnected-(U1-RF_BG-Pad31)") (class "Default")
      (node (ref "U1") (pin "31") (pinfunction "RF_BG_31") (pintype "bidirectional+no_connect"))
    )
  )
)
